# Pi5-Interface.net
KiCad netlist of a schematic drawn in Altium Designer
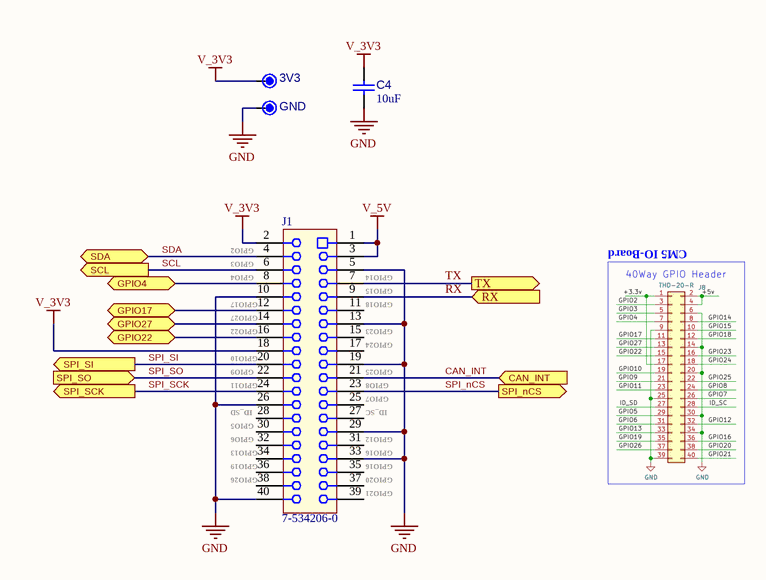
[diagram p0: Pi5-Interface.SchDoc]

(export (version "E")
  (design (tool "Eeschema 10.0.6"))
  (components
    (comp (ref "3V3")
      (value "DNP")
      (footprint "TP_TH061")
      (description "Pad TH 0.61mm diameter (AWG28)")
      (libsource (lib "243-436_MP_Console") (part "TP_TH0.61mm(AWG28)"))
    )
    (comp (ref "C4")
      (value "10uF")
      (footprint "C_2012[0805]")
      (description "Capacitor type 1")
      (fields (field (name "TOLERANCE") "10%") (field (name "Comment") "CAP CER 10uF 10V X7R 0805"))
      (libsource (lib "TEP-AltiumLib-Passives-RLC") (part "capacitor"))
    )
    (comp (ref "GND")
      (value "DNP")
      (footprint "TP_TH061")
      (description "Pad TH 0.61mm diameter (AWG28)")
      (libsource (lib "243-436_MP_Console") (part "TP_TH0.61mm(AWG28)"))
    )
    (comp (ref "J1")
      (value "7-534206-0")
      (footprint "CONN_Receptacle_2x20pos_100mil")
      (description "CONN SOCKET 2x20POS 2.54mm")
      (libsource (lib "TEP-AltiumLib-Connectors") (part "CONN-100MIL-SKT-02X20"))
    )
  )
  (nets
    (net (code "1") (name "/CAN_INT") (class "Default")
      (node (ref "J1") (pin "21") (pinfunction "21_21") (pintype "passive"))
    )
    (net (code "2") (name "/GPIO4") (class "Default")
      (node (ref "J1") (pin "8") (pinfunction "8_8") (pintype "passive"))
    )
    (net (code "3") (name "/GPIO17") (class "Default")
      (node (ref "J1") (pin "12") (pinfunction "12_12") (pintype "passive"))
    )
    (net (code "4") (name "/GPIO22") (class "Default")
      (node (ref "J1") (pin "16") (pinfunction "16_16") (pintype "passive"))
    )
    (net (code "5") (name "/GPIO27") (class "Default")
      (node (ref "J1") (pin "14") (pinfunction "14_14") (pintype "passive"))
    )
    (net (code "6") (name "/RX") (class "Default")
      (node (ref "J1") (pin "9") (pinfunction "9_9") (pintype "passive"))
    )
    (net (code "7") (name "/SCL") (class "Default")
      (node (ref "J1") (pin "6") (pinfunction "6_6") (pintype "passive"))
    )
    (net (code "8") (name "/SDA") (class "Default")
      (node (ref "J1") (pin "4") (pinfunction "4_4") (pintype "passive"))
    )
    (net (code "9") (name "/SPI_SCK") (class "Default")
      (node (ref "J1") (pin "24") (pinfunction "24_24") (pintype "passive"))
    )
    (net (code "10") (name "/SPI_SI") (class "Default")
      (node (ref "J1") (pin "20") (pinfunction "20_20") (pintype "passive"))
    )
    (net (code "11") (name "/SPI_SO") (class "Default")
      (node (ref "J1") (pin "22") (pinfunction "22_22") (pintype "passive"))
    )
    (net (code "12") (name "/SPI_nCS") (class "Default")
      (node (ref "J1") (pin "23") (pinfunction "23_23") (pintype "passive"))
    )
    (net (code "13") (name "/TX") (class "Default")
      (node (ref "J1") (pin "7") (pinfunction "7_7") (pintype "passive"))
    )
    (net (code "14") (name "GND") (class "Default")
      (node (ref "C4") (pin "1") (pinfunction "1_1") (pintype "passive"))
      (node (ref "GND") (pin "1") (pinfunction "1_1") (pintype "passive"))
      (node (ref "J1") (pin "10") (pinfunction "10_10") (pintype "passive"))
      (node (ref "J1") (pin "13") (pinfunction "13_13") (pintype "passive"))
      (node (ref "J1") (pin "19") (pinfunction "19_19") (pintype "passive"))
      (node (ref "J1") (pin "26") (pinfunction "26_26") (pintype "passive"))
      (node (ref "J1") (pin "29") (pinfunction "29_29") (pintype "passive"))
      (node (ref "J1") (pin "33") (pinfunction "33_33") (pintype "passive"))
      (node (ref "J1") (pin "40") (pinfunction "40_40") (pintype "passive"))
      (node (ref "J1") (pin "5") (pinfunction "5_5") (pintype "passive"))
    )
    (net (code "15") (name "V_3V3") (class "Default")
      (node (ref "3V3") (pin "1") (pinfunction "1_1") (pintype "passive"))
      (node (ref "C4") (pin "2") (pinfunction "2_2") (pintype "passive"))
      (node (ref "J1") (pin "18") (pinfunction "18_18") (pintype "passive"))
      (node (ref "J1") (pin "2") (pinfunction "2_2") (pintype "passive"))
    )
    (net (code "16") (name "V_5V") (class "Default")
      (node (ref "J1") (pin "1") (pinfunction "1_1") (pintype "passive"))
      (node (ref "J1") (pin "3") (pinfunction "3_3") (pintype "passive"))
    )
    (net (code "17") (name "unconnected-(J1-Pad11)") (class "Default")
      (node (ref "J1") (pin "11") (pinfunction "11_11") (pintype "passive"))
    )
    (net (code "18") (name "unconnected-(J1-Pad15)") (class "Default")
      (node (ref "J1") (pin "15") (pinfunction "15_15") (pintype "passive"))
    )
    (net (code "19") (name "unconnected-(J1-Pad17)") (class "Default")
      (node (ref "J1") (pin "17") (pinfunction "17_17") (pintype "passive"))
    )
    (net (code "20") (name "unconnected-(J1-Pad25)") (class "Default")
      (node (ref "J1") (pin "25") (pinfunction "25_25") (pintype "passive"))
    )
    (net (code "21") (name "unconnected-(J1-Pad27)") (class "Default")
      (node (ref "J1") (pin "27") (pinfunction "27_27") (pintype "passive"))
    )
    (net (code "22") (name "unconnected-(J1-Pad28)") (class "Default")
      (node (ref "J1") (pin "28") (pinfunction "28_28") (pintype "passive"))
    )
    (net (code "23") (name "unconnected-(J1-Pad30)") (class "Default")
      (node (ref "J1") (pin "30") (pinfunction "30_30") (pintype "passive"))
    )
    (net (code "24") (name "unconnected-(J1-Pad31)") (class "Default")
      (node (ref "J1") (pin "31") (pinfunction "31_31") (pintype "passive"))
    )
    (net (code "25") (name "unconnected-(J1-Pad32)") (class "Default")
      (node (ref "J1") (pin "32") (pinfunction "32_32") (pintype "passive"))
    )
    (net (code "26") (name "unconnected-(J1-Pad34)") (class "Default")
      (node (ref "J1") (pin "34") (pinfunction "34_34") (pintype "passive"))
    )
    (net (code "27") (name "unconnected-(J1-Pad35)") (class "Default")
      (node (ref "J1") (pin "35") (pinfunction "35_35") (pintype "passive"))
    )
    (net (code "28") (name "unconnected-(J1-Pad36)") (class "Default")
      (node (ref "J1") (pin "36") (pinfunction "36_36") (pintype "passive"))
    )
    (net (code "29") (name "unconnected-(J1-Pad37)") (class "Default")
      (node (ref "J1") (pin "37") (pinfunction "37_37") (pintype "passive"))
    )
    (net (code "30") (name "unconnected-(J1-Pad38)") (class "Default")
      (node (ref "J1") (pin "38") (pinfunction "38_38") (pintype "passive"))
    )
    (net (code "31") (name "unconnected-(J1-Pad39)") (class "Default")
      (node (ref "J1") (pin "39") (pinfunction "39_39") (pintype "passive"))
    )
  )
)
